# iv-11_boost_supply.net
KiCad netlist of a schematic drawn in EAGLE
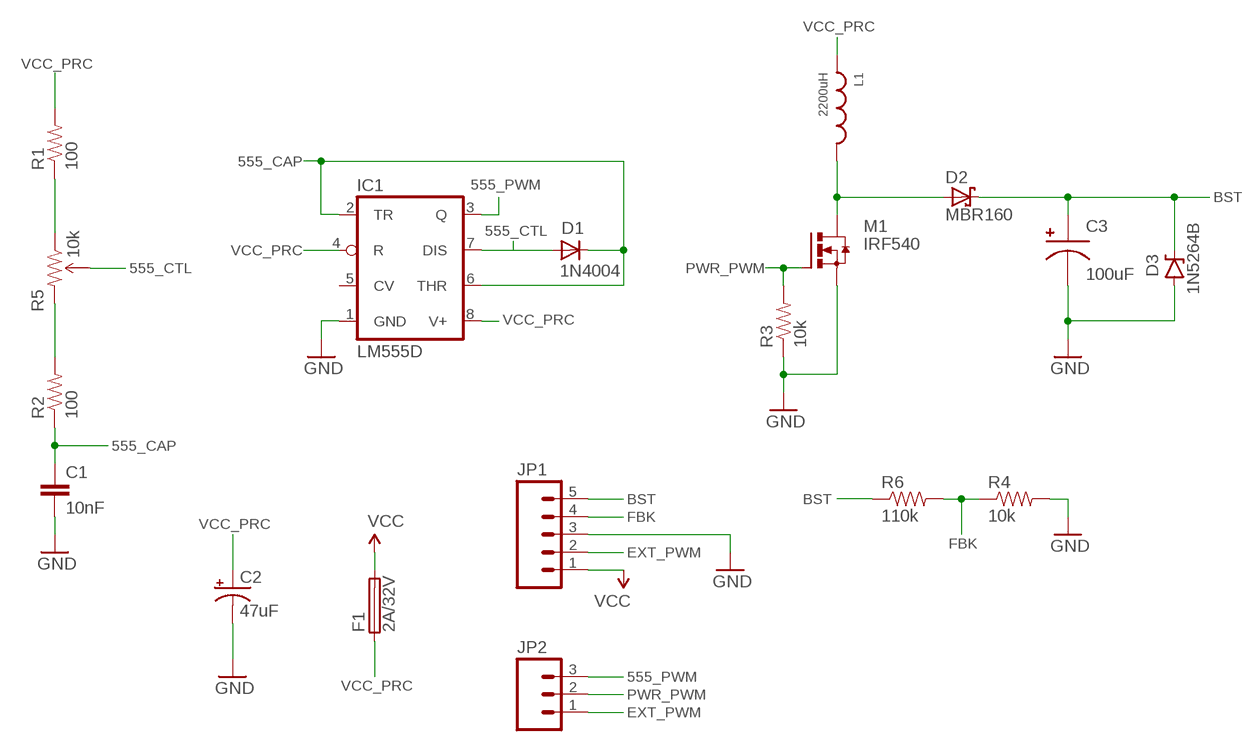
[diagram p0: schematic, sheet 1]

(export (version "E")
  (design (tool "Eeschema 10.0.6"))
  (components
    (comp (ref "C1")
      (value "10nF")
      (footprint "eagle-import:1206")
      (libsource (lib "eagle-import") (part "CAP1206"))
    )
    (comp (ref "C2")
      (value "47uF")
      (footprint "eagle-import:CPOL-RADIAL-100UF-25V")
      (libsource (lib "eagle-import") (part "CAP_POLPTH1"))
    )
    (comp (ref "C3")
      (value "100uF")
      (footprint "eagle-import:POLAR-CAP-PTH-10MM")
      (libsource (lib "eagle-import") (part "POLAR-CAP"))
    )
    (comp (ref "D1")
      (value "1N4004")
      (footprint "eagle-import:DO41-10")
      (libsource (lib "eagle-import") (part "1N4004"))
    )
    (comp (ref "D2")
      (value "MBR160")
      (footprint "eagle-import:DO41-10")
      (libsource (lib "eagle-import") (part "SCHOTTKY-DIODEDO41"))
    )
    (comp (ref "D3")
      (value "1N5264B")
      (footprint "eagle-import:DIODE-ZENER")
      (libsource (lib "eagle-import") (part "DIODE-ZENERPTH"))
    )
    (comp (ref "F1")
      (value "2A/32V")
      (footprint "eagle-import:1AG-1_4X5_8-FUSE")
      (libsource (lib "eagle-import") (part "1AG-1/4X5/8-FUSE"))
    )
    (comp (ref "IC1")
      (value "LM555D")
      (footprint "eagle-import:SO08")
      (libsource (lib "eagle-import") (part "555DLM"))
    )
    (comp (ref "JP1")
      (value "M05LOCK")
      (footprint "eagle-import:1X05_LOCK")
      (libsource (lib "eagle-import") (part "M05LOCK"))
    )
    (comp (ref "JP2")
      (value "M03LOCK")
      (footprint "eagle-import:1X03_LOCK")
      (libsource (lib "eagle-import") (part "M03LOCK"))
    )
    (comp (ref "L1")
      (value "2200uH")
      (footprint "eagle-import:INDUCTOR-PTH-13MM")
      (libsource (lib "eagle-import") (part "INDUCTOR"))
    )
    (comp (ref "M1")
      (value "IRF540")
      (footprint "eagle-import:D2PACK")
      (libsource (lib "eagle-import") (part "IRF540NPBF"))
    )
    (comp (ref "R1")
      (value "100")
      (footprint "eagle-import:1206")
      (libsource (lib "eagle-import") (part "RESISTOR1206"))
    )
    (comp (ref "R2")
      (value "100")
      (footprint "eagle-import:1206")
      (libsource (lib "eagle-import") (part "RESISTOR1206"))
    )
    (comp (ref "R3")
      (value "10k")
      (footprint "eagle-import:1206")
      (libsource (lib "eagle-import") (part "RESISTOR1206"))
    )
    (comp (ref "R4")
      (value "10k")
      (footprint "eagle-import:1206")
      (libsource (lib "eagle-import") (part "RESISTOR1206"))
    )
    (comp (ref "R5")
      (value "10k")
      (footprint "eagle-import:TRIMPOT-5MM-V2")
      (libsource (lib "eagle-import") (part "TRIMPOT"))
    )
    (comp (ref "R6")
      (value "110k")
      (footprint "eagle-import:1206")
      (libsource (lib "eagle-import") (part "RESISTOR1206"))
    )
  )
  (nets
    (net (code "1") (name "/555_CAP") (class "Default")
      (node (ref "C1") (pin "1") (pinfunction "1_1") (pintype "passive"))
      (node (ref "D1") (pin "C") (pinfunction "C_C") (pintype "passive"))
      (node (ref "IC1") (pin "2") (pinfunction "TR_2") (pintype "input"))
      (node (ref "IC1") (pin "6") (pinfunction "THR_6") (pintype "input"))
      (node (ref "R2") (pin "1") (pinfunction "1_1") (pintype "passive"))
    )
    (net (code "2") (name "/555_CTL") (class "Default")
      (node (ref "D1") (pin "A") (pinfunction "A_A") (pintype "passive"))
      (node (ref "IC1") (pin "7") (pinfunction "DIS_7") (pintype "input"))
      (node (ref "R5") (pin "B") (pinfunction "WIPER_B") (pintype "passive"))
    )
    (net (code "3") (name "/555_PWM") (class "Default")
      (node (ref "IC1") (pin "3") (pinfunction "Q_3") (pintype "output"))
      (node (ref "JP2") (pin "3") (pinfunction "3_3") (pintype "passive"))
    )
    (net (code "4") (name "/BST") (class "Default")
      (node (ref "C3") (pin "A") (pinfunction "A_A") (pintype "bidirectional"))
      (node (ref "D2") (pin "C") (pinfunction "C_C") (pintype "passive"))
      (node (ref "D3") (pin "P$1") (pinfunction "C_P$1") (pintype "passive"))
      (node (ref "JP1") (pin "5") (pinfunction "5_5") (pintype "passive"))
      (node (ref "R6") (pin "1") (pinfunction "1_1") (pintype "passive"))
    )
    (net (code "5") (name "/EXT_PWM") (class "Default")
      (node (ref "JP1") (pin "2") (pinfunction "2_2") (pintype "passive"))
      (node (ref "JP2") (pin "1") (pinfunction "1_1") (pintype "passive"))
    )
    (net (code "6") (name "/FBK") (class "Default")
      (node (ref "JP1") (pin "4") (pinfunction "4_4") (pintype "passive"))
      (node (ref "R4") (pin "1") (pinfunction "1_1") (pintype "passive"))
      (node (ref "R6") (pin "2") (pinfunction "2_2") (pintype "passive"))
    )
    (net (code "7") (name "/PWR_PWM") (class "Default")
      (node (ref "JP2") (pin "2") (pinfunction "2_2") (pintype "passive"))
      (node (ref "M1") (pin "1") (pinfunction "G_1") (pintype "passive"))
      (node (ref "R3") (pin "2") (pinfunction "2_2") (pintype "passive"))
    )
    (net (code "8") (name "/VCC_PRC") (class "Default")
      (node (ref "C2") (pin "1") (pinfunction "+_1") (pintype "passive"))
      (node (ref "F1") (pin "P$1") (pinfunction "1_P$1") (pintype "passive"))
      (node (ref "F1") (pin "P$2") (pinfunction "1_P$2") (pintype "passive"))
      (node (ref "IC1") (pin "4") (pinfunction "R_4") (pintype "input"))
      (node (ref "IC1") (pin "8") (pinfunction "V+_8") (pintype "power_in"))
      (node (ref "L1") (pin "A") (pinfunction "A_A") (pintype "bidirectional"))
      (node (ref "R1") (pin "2") (pinfunction "2_2") (pintype "passive"))
    )
    (net (code "9") (name "GND") (class "Default")
      (node (ref "C1") (pin "2") (pinfunction "2_2") (pintype "passive"))
      (node (ref "C2") (pin "2") (pinfunction "-_2") (pintype "passive"))
      (node (ref "C3") (pin "B") (pinfunction "B_B") (pintype "bidirectional"))
      (node (ref "D3") (pin "P$2") (pinfunction "A_P$2") (pintype "passive"))
      (node (ref "IC1") (pin "1") (pinfunction "GND_1") (pintype "power_in"))
      (node (ref "JP1") (pin "3") (pinfunction "3_3") (pintype "passive"))
      (node (ref "M1") (pin "3") (pinfunction "S_3") (pintype "passive"))
      (node (ref "R3") (pin "1") (pinfunction "1_1") (pintype "passive"))
      (node (ref "R4") (pin "2") (pinfunction "2_2") (pintype "passive"))
    )
    (net (code "10") (name "Net-(M1-D)") (class "Default")
      (node (ref "D2") (pin "A") (pinfunction "A_A") (pintype "passive"))
      (node (ref "L1") (pin "B") (pinfunction "B_B") (pintype "bidirectional"))
      (node (ref "M1") (pin "2") (pinfunction "D_2") (pintype "passive"))
    )
    (net (code "11") (name "Net-(R5-CCW)") (class "Default")
      (node (ref "R1") (pin "1") (pinfunction "1_1") (pintype "passive"))
      (node (ref "R5") (pin "A") (pinfunction "CCW_A") (pintype "passive"))
    )
    (net (code "12") (name "Net-(R5-CW)") (class "Default")
      (node (ref "R2") (pin "2") (pinfunction "2_2") (pintype "passive"))
      (node (ref "R5") (pin "C") (pinfunction "CW_C") (pintype "passive"))
    )
    (net (code "13") (name "VCC") (class "Default")
      (node (ref "F1") (pin "P$3") (pinfunction "2_P$3") (pintype "passive"))
      (node (ref "F1") (pin "P$4") (pinfunction "2_P$4") (pintype "passive"))
      (node (ref "JP1") (pin "1") (pinfunction "1_1") (pintype "passive"))
    )
    (net (code "14") (name "unconnected-(IC1-CV-Pad5)") (class "Default")
      (node (ref "IC1") (pin "5") (pinfunction "CV_5") (pintype "input"))
    )
  )
)
